# Flight_Computer_R2.net
KiCad netlist of a schematic drawn in EAGLE
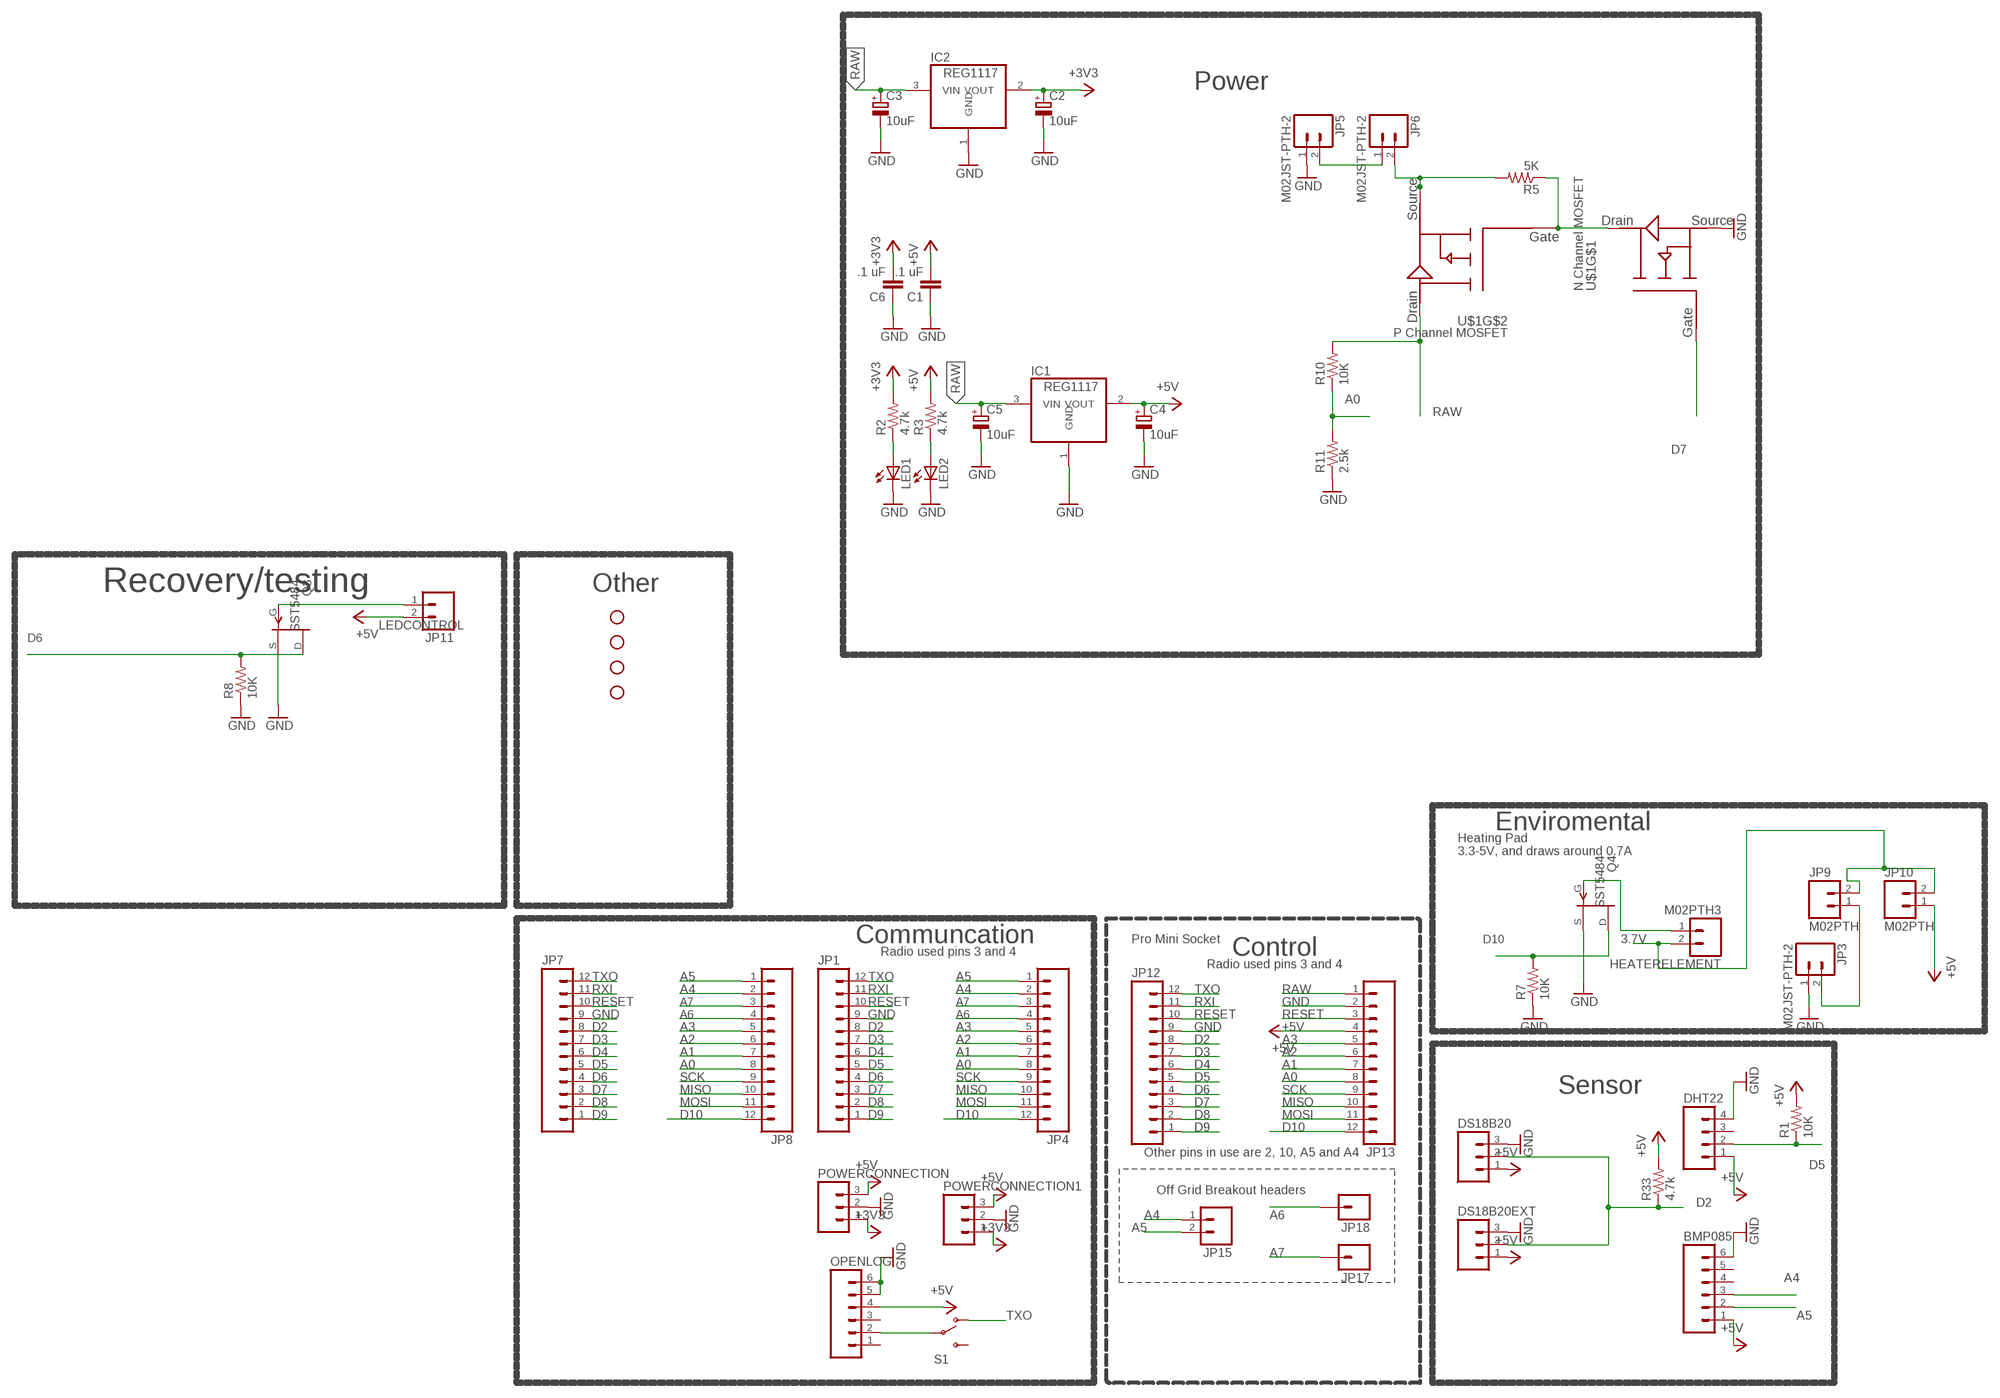
[diagram p0: schematic, sheet 1]

(export (version "E")
  (design (tool "Eeschema 10.0.6"))
  (components
    (comp (ref "BMP085")
      (value "M06SIP")
      (footprint "eagle-import:1X06")
      (libsource (lib "eagle-import") (part "M06SIP"))
    )
    (comp (ref "C1")
      (value ".1 uF")
      (footprint "eagle-import:1206")
      (libsource (lib "eagle-import") (part "CAP1206"))
    )
    (comp (ref "C2")
      (value "10uF")
      (footprint "eagle-import:E2,5-5")
      (libsource (lib "eagle-import") (part "CPOL-EUE2.5-5"))
    )
    (comp (ref "C3")
      (value "10uF")
      (footprint "eagle-import:E2,5-5")
      (libsource (lib "eagle-import") (part "CPOL-EUE2.5-5"))
    )
    (comp (ref "C4")
      (value "10uF")
      (footprint "eagle-import:E2,5-5")
      (libsource (lib "eagle-import") (part "CPOL-EUE2.5-5"))
    )
    (comp (ref "C5")
      (value "10uF")
      (footprint "eagle-import:E2,5-5")
      (libsource (lib "eagle-import") (part "CPOL-EUE2.5-5"))
    )
    (comp (ref "C6")
      (value ".1 uF")
      (footprint "eagle-import:1206")
      (libsource (lib "eagle-import") (part "CAP1206"))
    )
    (comp (ref "DHT22")
      (value "M041X04_NO_SILK")
      (footprint "eagle-import:1X04_NO_SILK")
      (libsource (lib "eagle-import") (part "M041X04_NO_SILK"))
    )
    (comp (ref "DS18B20")
      (value "M03PTH")
      (footprint "eagle-import:1X03")
      (libsource (lib "eagle-import") (part "M03PTH"))
    )
    (comp (ref "DS18B20EXT")
      (value "M03PTH")
      (footprint "eagle-import:1X03")
      (libsource (lib "eagle-import") (part "M03PTH"))
    )
    (comp (ref "HEATERELEMENT")
      (value "M02PTH3")
      (footprint "eagle-import:1X02_LONGPADS")
      (libsource (lib "eagle-import") (part "SparkFun-Connectors_M02PTH3"))
    )
    (comp (ref "IC1")
      (value "REG1117")
      (footprint "eagle-import:SOT223")
      (libsource (lib "eagle-import") (part "REG1117"))
    )
    (comp (ref "IC2")
      (value "REG1117")
      (footprint "eagle-import:SOT223")
      (libsource (lib "eagle-import") (part "REG1117"))
    )
    (comp (ref "JP1")
      (value "M12PTH")
      (footprint "eagle-import:1X12")
      (libsource (lib "eagle-import") (part "M12PTH"))
    )
    (comp (ref "JP3")
      (value "M02JST-PTH-2")
      (footprint "eagle-import:JST-2-PTH")
      (libsource (lib "eagle-import") (part "SparkFun-Connectors_M02JST-PTH-2"))
    )
    (comp (ref "JP4")
      (value "M12PTH")
      (footprint "eagle-import:1X12")
      (libsource (lib "eagle-import") (part "M12PTH"))
    )
    (comp (ref "JP5")
      (value "M02JST-PTH-2")
      (footprint "eagle-import:JST-2-PTH")
      (libsource (lib "eagle-import") (part "SparkFun-Connectors_M02JST-PTH-2"))
    )
    (comp (ref "JP6")
      (value "M02JST-PTH-2")
      (footprint "eagle-import:JST-2-PTH")
      (libsource (lib "eagle-import") (part "SparkFun-Connectors_M02JST-PTH-2"))
    )
    (comp (ref "JP7")
      (value "M12PTH")
      (footprint "eagle-import:1X12")
      (libsource (lib "eagle-import") (part "M12PTH"))
    )
    (comp (ref "JP8")
      (value "M12PTH")
      (footprint "eagle-import:1X12")
      (libsource (lib "eagle-import") (part "M12PTH"))
    )
    (comp (ref "JP9")
      (value "M02PTH")
      (footprint "eagle-import:1X02")
      (libsource (lib "eagle-import") (part "SparkFun-Connectors_M02PTH"))
    )
    (comp (ref "JP10")
      (value "M02PTH")
      (footprint "eagle-import:1X02")
      (libsource (lib "eagle-import") (part "SparkFun-Connectors_M02PTH"))
    )
    (comp (ref "JP11")
      (value "M02PTH")
      (footprint "eagle-import:1X02")
      (libsource (lib "eagle-import") (part "M02PTH"))
    )
    (comp (ref "JP12")
      (value "M12PTH")
      (footprint "eagle-import:1X12")
      (libsource (lib "eagle-import") (part "M12PTH"))
    )
    (comp (ref "JP13")
      (value "M12PTH")
      (footprint "eagle-import:1X12")
      (libsource (lib "eagle-import") (part "M12PTH"))
    )
    (comp (ref "JP15")
      (value "M02PTH")
      (footprint "eagle-import:1X02")
      (libsource (lib "eagle-import") (part "M02PTH"))
    )
    (comp (ref "JP17")
      (value "M01PTH")
      (footprint "eagle-import:1X01")
      (libsource (lib "eagle-import") (part "M01PTH"))
    )
    (comp (ref "JP18")
      (value "M01PTH")
      (footprint "eagle-import:1X01")
      (libsource (lib "eagle-import") (part "M01PTH"))
    )
    (comp (ref "LED1")
      (value "LED3MM")
      (footprint "eagle-import:LED3MM")
      (libsource (lib "eagle-import") (part "LED3MM"))
    )
    (comp (ref "LED2")
      (value "LED3MM")
      (footprint "eagle-import:LED3MM")
      (libsource (lib "eagle-import") (part "LED3MM"))
    )
    (comp (ref "OPENLOG")
      (value "M06SIP")
      (footprint "eagle-import:1X06")
      (libsource (lib "eagle-import") (part "M06SIP"))
    )
    (comp (ref "POWERCONNECTION")
      (value "M03PTH")
      (footprint "eagle-import:1X03")
      (libsource (lib "eagle-import") (part "M03PTH"))
    )
    (comp (ref "POWERCONNECTION1")
      (value "M03PTH")
      (footprint "eagle-import:1X03")
      (libsource (lib "eagle-import") (part "M03PTH"))
    )
    (comp (ref "Q3")
      (value "SST5484")
      (footprint "eagle-import:SOT23")
      (libsource (lib "eagle-import") (part "?548SST4"))
    )
    (comp (ref "Q4")
      (value "SST5484")
      (footprint "eagle-import:SOT23")
      (libsource (lib "eagle-import") (part "?548SST4"))
    )
    (comp (ref "R1")
      (value "10K")
      (footprint "eagle-import:1206")
      (libsource (lib "eagle-import") (part "RESISTOR1206"))
    )
    (comp (ref "R2")
      (value "4.7k")
      (footprint "eagle-import:1206")
      (libsource (lib "eagle-import") (part "RESISTOR1206"))
    )
    (comp (ref "R3")
      (value "4.7k")
      (footprint "eagle-import:1206")
      (libsource (lib "eagle-import") (part "RESISTOR1206"))
    )
    (comp (ref "R5")
      (value "5K")
      (footprint "eagle-import:1206")
      (libsource (lib "eagle-import") (part "RESISTOR1206"))
    )
    (comp (ref "R7")
      (value "10K")
      (footprint "eagle-import:1206")
      (libsource (lib "eagle-import") (part "RESISTOR1206"))
    )
    (comp (ref "R8")
      (value "10K")
      (footprint "eagle-import:1206")
      (libsource (lib "eagle-import") (part "RESISTOR1206"))
    )
    (comp (ref "R10")
      (value "10K")
      (footprint "eagle-import:1206")
      (libsource (lib "eagle-import") (part "RESISTOR1206"))
    )
    (comp (ref "R11")
      (value "2.5k")
      (footprint "eagle-import:1206")
      (libsource (lib "eagle-import") (part "RESISTOR1206"))
    )
    (comp (ref "R33")
      (value "4.7k")
      (footprint "eagle-import:1206")
      (libsource (lib "eagle-import") (part "RESISTOR1206"))
    )
    (comp (ref "S1")
      (value "SWITCH-SPDTPTH")
      (footprint "eagle-import:SWITCH-SPDT")
      (libsource (lib "eagle-import") (part "SWITCH-SPDTPTH"))
    )
    (comp (ref "STANDOFF1")
      (value "STAND-OFF")
      (footprint "eagle-import:STAND-OFF")
      (libsource (lib "eagle-import") (part "STAND-OFF"))
    )
    (comp (ref "STANDOFF2")
      (value "STAND-OFF")
      (footprint "eagle-import:STAND-OFF")
      (libsource (lib "eagle-import") (part "STAND-OFF"))
    )
    (comp (ref "STANDOFF3")
      (value "STAND-OFF")
      (footprint "eagle-import:STAND-OFF")
      (libsource (lib "eagle-import") (part "STAND-OFF"))
    )
    (comp (ref "STANDOFF4")
      (value "STAND-OFF")
      (footprint "eagle-import:STAND-OFF")
      (libsource (lib "eagle-import") (part "STAND-OFF"))
    )
    (comp (ref "U$1")
      (value "IRF9389TRPBF")
      (footprint "eagle-import:SO-8")
      (libsource (lib "eagle-import") (part "IRF9389TRPBF"))
    )
  )
  (nets
    (net (code "1") (name "+3V3") (class "Default")
      (node (ref "C2") (pin "+") (pinfunction "+_+") (pintype "passive"))
      (node (ref "C6") (pin "2") (pinfunction "2_2") (pintype "passive"))
      (node (ref "IC2") (pin "2") (pinfunction "VOUT_2") (pintype "output"))
      (node (ref "POWERCONNECTION") (pin "1") (pinfunction "1_1") (pintype "passive"))
      (node (ref "POWERCONNECTION1") (pin "1") (pinfunction "1_1") (pintype "passive"))
      (node (ref "R2") (pin "2") (pinfunction "2_2") (pintype "passive"))
    )
    (net (code "2") (name "+5V") (class "Default")
      (node (ref "BMP085") (pin "1") (pinfunction "1_1") (pintype "passive"))
      (node (ref "C1") (pin "2") (pinfunction "2_2") (pintype "passive"))
      (node (ref "C4") (pin "+") (pinfunction "+_+") (pintype "passive"))
      (node (ref "DHT22") (pin "1") (pinfunction "1_1") (pintype "passive"))
      (node (ref "DS18B20") (pin "1") (pinfunction "1_1") (pintype "passive"))
      (node (ref "DS18B20EXT") (pin "1") (pinfunction "1_1") (pintype "passive"))
      (node (ref "IC1") (pin "2") (pinfunction "VOUT_2") (pintype "output"))
      (node (ref "JP10") (pin "1") (pinfunction "1_1") (pintype "passive"))
      (node (ref "JP11") (pin "2") (pinfunction "2_2") (pintype "passive"))
      (node (ref "JP13") (pin "4") (pinfunction "4_4") (pintype "passive"))
      (node (ref "OPENLOG") (pin "4") (pinfunction "4_4") (pintype "passive"))
      (node (ref "POWERCONNECTION") (pin "3") (pinfunction "3_3") (pintype "passive"))
      (node (ref "POWERCONNECTION1") (pin "3") (pinfunction "3_3") (pintype "passive"))
      (node (ref "R1") (pin "2") (pinfunction "2_2") (pintype "passive"))
      (node (ref "R3") (pin "2") (pinfunction "2_2") (pintype "passive"))
      (node (ref "R33") (pin "2") (pinfunction "2_2") (pintype "passive"))
    )
    (net (code "3") (name "/3.7V") (class "Default")
      (node (ref "HEATERELEMENT") (pin "2") (pinfunction "2_2") (pintype "passive"))
      (node (ref "JP10") (pin "2") (pinfunction "2_2") (pintype "passive"))
      (node (ref "JP9") (pin "2") (pinfunction "2_2") (pintype "passive"))
    )
    (net (code "4") (name "/A0") (class "Default")
      (node (ref "JP13") (pin "8") (pinfunction "8_8") (pintype "passive"))
      (node (ref "JP4") (pin "8") (pinfunction "8_8") (pintype "passive"))
      (node (ref "JP8") (pin "8") (pinfunction "8_8") (pintype "passive"))
      (node (ref "R10") (pin "1") (pinfunction "1_1") (pintype "passive"))
      (node (ref "R11") (pin "2") (pinfunction "2_2") (pintype "passive"))
    )
    (net (code "5") (name "/A1") (class "Default")
      (node (ref "JP13") (pin "7") (pinfunction "7_7") (pintype "passive"))
      (node (ref "JP4") (pin "7") (pinfunction "7_7") (pintype "passive"))
      (node (ref "JP8") (pin "7") (pinfunction "7_7") (pintype "passive"))
    )
    (net (code "6") (name "/A2") (class "Default")
      (node (ref "JP13") (pin "6") (pinfunction "6_6") (pintype "passive"))
      (node (ref "JP4") (pin "6") (pinfunction "6_6") (pintype "passive"))
      (node (ref "JP8") (pin "6") (pinfunction "6_6") (pintype "passive"))
    )
    (net (code "7") (name "/A3") (class "Default")
      (node (ref "JP13") (pin "5") (pinfunction "5_5") (pintype "passive"))
      (node (ref "JP4") (pin "5") (pinfunction "5_5") (pintype "passive"))
      (node (ref "JP8") (pin "5") (pinfunction "5_5") (pintype "passive"))
    )
    (net (code "8") (name "/A4") (class "Default")
      (node (ref "BMP085") (pin "3") (pinfunction "3_3") (pintype "passive"))
      (node (ref "JP15") (pin "1") (pinfunction "1_1") (pintype "passive"))
      (node (ref "JP4") (pin "2") (pinfunction "2_2") (pintype "passive"))
      (node (ref "JP8") (pin "2") (pinfunction "2_2") (pintype "passive"))
    )
    (net (code "9") (name "/A5") (class "Default")
      (node (ref "BMP085") (pin "2") (pinfunction "2_2") (pintype "passive"))
      (node (ref "JP15") (pin "2") (pinfunction "2_2") (pintype "passive"))
      (node (ref "JP4") (pin "1") (pinfunction "1_1") (pintype "passive"))
      (node (ref "JP8") (pin "1") (pinfunction "1_1") (pintype "passive"))
    )
    (net (code "10") (name "/A6") (class "Default")
      (node (ref "JP18") (pin "1") (pinfunction "1_1") (pintype "passive"))
      (node (ref "JP4") (pin "4") (pinfunction "4_4") (pintype "passive"))
      (node (ref "JP8") (pin "4") (pinfunction "4_4") (pintype "passive"))
    )
    (net (code "11") (name "/A7") (class "Default")
      (node (ref "JP17") (pin "1") (pinfunction "1_1") (pintype "passive"))
      (node (ref "JP4") (pin "3") (pinfunction "3_3") (pintype "passive"))
      (node (ref "JP8") (pin "3") (pinfunction "3_3") (pintype "passive"))
    )
    (net (code "12") (name "/D2") (class "Default")
      (node (ref "DS18B20") (pin "2") (pinfunction "2_2") (pintype "passive"))
      (node (ref "DS18B20EXT") (pin "2") (pinfunction "2_2") (pintype "passive"))
      (node (ref "JP1") (pin "8") (pinfunction "8_8") (pintype "passive"))
      (node (ref "JP12") (pin "8") (pinfunction "8_8") (pintype "passive"))
      (node (ref "JP7") (pin "8") (pinfunction "8_8") (pintype "passive"))
      (node (ref "R33") (pin "1") (pinfunction "1_1") (pintype "passive"))
    )
    (net (code "13") (name "/D3") (class "Default")
      (node (ref "JP1") (pin "7") (pinfunction "7_7") (pintype "passive"))
      (node (ref "JP12") (pin "7") (pinfunction "7_7") (pintype "passive"))
      (node (ref "JP7") (pin "7") (pinfunction "7_7") (pintype "passive"))
    )
    (net (code "14") (name "/D4") (class "Default")
      (node (ref "JP1") (pin "6") (pinfunction "6_6") (pintype "passive"))
      (node (ref "JP12") (pin "6") (pinfunction "6_6") (pintype "passive"))
      (node (ref "JP7") (pin "6") (pinfunction "6_6") (pintype "passive"))
    )
    (net (code "15") (name "/D5") (class "Default")
      (node (ref "DHT22") (pin "2") (pinfunction "2_2") (pintype "passive"))
      (node (ref "JP1") (pin "5") (pinfunction "5_5") (pintype "passive"))
      (node (ref "JP12") (pin "5") (pinfunction "5_5") (pintype "passive"))
      (node (ref "JP7") (pin "5") (pinfunction "5_5") (pintype "passive"))
      (node (ref "R1") (pin "1") (pinfunction "1_1") (pintype "passive"))
    )
    (net (code "16") (name "/D6") (class "Default")
      (node (ref "JP1") (pin "4") (pinfunction "4_4") (pintype "passive"))
      (node (ref "JP12") (pin "4") (pinfunction "4_4") (pintype "passive"))
      (node (ref "JP7") (pin "4") (pinfunction "4_4") (pintype "passive"))
      (node (ref "Q3") (pin "1") (pinfunction "D_1") (pintype "passive"))
      (node (ref "R8") (pin "2") (pinfunction "2_2") (pintype "passive"))
    )
    (net (code "17") (name "/D7") (class "Default")
      (node (ref "JP1") (pin "3") (pinfunction "3_3") (pintype "passive"))
      (node (ref "JP12") (pin "3") (pinfunction "3_3") (pintype "passive"))
      (node (ref "JP7") (pin "3") (pinfunction "3_3") (pintype "passive"))
      (node (ref "U$1") (pin "2") (pinfunction "GATE_2") (pintype "input"))
    )
    (net (code "18") (name "/D8") (class "Default")
      (node (ref "JP1") (pin "2") (pinfunction "2_2") (pintype "passive"))
      (node (ref "JP12") (pin "2") (pinfunction "2_2") (pintype "passive"))
      (node (ref "JP7") (pin "2") (pinfunction "2_2") (pintype "passive"))
    )
    (net (code "19") (name "/D9") (class "Default")
      (node (ref "JP1") (pin "1") (pinfunction "1_1") (pintype "passive"))
      (node (ref "JP12") (pin "1") (pinfunction "1_1") (pintype "passive"))
      (node (ref "JP7") (pin "1") (pinfunction "1_1") (pintype "passive"))
    )
    (net (code "20") (name "/D10") (class "Default")
      (node (ref "JP13") (pin "12") (pinfunction "12_12") (pintype "passive"))
      (node (ref "JP4") (pin "12") (pinfunction "12_12") (pintype "passive"))
      (node (ref "JP8") (pin "12") (pinfunction "12_12") (pintype "passive"))
      (node (ref "Q4") (pin "1") (pinfunction "D_1") (pintype "passive"))
      (node (ref "R7") (pin "2") (pinfunction "2_2") (pintype "passive"))
    )
    (net (code "21") (name "/LEDCONTROL") (class "Default")
      (node (ref "JP11") (pin "1") (pinfunction "1_1") (pintype "passive"))
      (node (ref "Q3") (pin "3") (pinfunction "G_3") (pintype "passive"))
    )
    (net (code "22") (name "/MISO") (class "Default")
      (node (ref "JP13") (pin "10") (pinfunction "10_10") (pintype "passive"))
      (node (ref "JP4") (pin "10") (pinfunction "10_10") (pintype "passive"))
      (node (ref "JP8") (pin "10") (pinfunction "10_10") (pintype "passive"))
    )
    (net (code "23") (name "/MOSI") (class "Default")
      (node (ref "JP13") (pin "11") (pinfunction "11_11") (pintype "passive"))
      (node (ref "JP4") (pin "11") (pinfunction "11_11") (pintype "passive"))
      (node (ref "JP8") (pin "11") (pinfunction "11_11") (pintype "passive"))
    )
    (net (code "24") (name "/RESET") (class "Default")
      (node (ref "JP1") (pin "10") (pinfunction "10_10") (pintype "passive"))
      (node (ref "JP12") (pin "10") (pinfunction "10_10") (pintype "passive"))
      (node (ref "JP13") (pin "3") (pinfunction "3_3") (pintype "passive"))
      (node (ref "JP7") (pin "10") (pinfunction "10_10") (pintype "passive"))
    )
    (net (code "25") (name "/RXI") (class "Default")
      (node (ref "JP1") (pin "11") (pinfunction "11_11") (pintype "passive"))
      (node (ref "JP12") (pin "11") (pinfunction "11_11") (pintype "passive"))
      (node (ref "JP7") (pin "11") (pinfunction "11_11") (pintype "passive"))
    )
    (net (code "26") (name "/SCK") (class "Default")
      (node (ref "JP13") (pin "9") (pinfunction "9_9") (pintype "passive"))
      (node (ref "JP4") (pin "9") (pinfunction "9_9") (pintype "passive"))
      (node (ref "JP8") (pin "9") (pinfunction "9_9") (pintype "passive"))
    )
    (net (code "27") (name "/TXO") (class "Default")
      (node (ref "JP1") (pin "12") (pinfunction "12_12") (pintype "passive"))
      (node (ref "JP12") (pin "12") (pinfunction "12_12") (pintype "passive"))
      (node (ref "JP7") (pin "12") (pinfunction "12_12") (pintype "passive"))
      (node (ref "S1") (pin "1") (pinfunction "O_1") (pintype "passive"))
    )
    (net (code "28") (name "GND") (class "Default")
      (node (ref "BMP085") (pin "6") (pinfunction "6_6") (pintype "passive"))
      (node (ref "C1") (pin "1") (pinfunction "1_1") (pintype "passive"))
      (node (ref "C2") (pin "-") (pinfunction "-_-") (pintype "passive"))
      (node (ref "C3") (pin "-") (pinfunction "-_-") (pintype "passive"))
      (node (ref "C4") (pin "-") (pinfunction "-_-") (pintype "passive"))
      (node (ref "C5") (pin "-") (pinfunction "-_-") (pintype "passive"))
      (node (ref "C6") (pin "1") (pinfunction "1_1") (pintype "passive"))
      (node (ref "DHT22") (pin "4") (pinfunction "4_4") (pintype "passive"))
      (node (ref "DS18B20") (pin "3") (pinfunction "3_3") (pintype "passive"))
      (node (ref "DS18B20EXT") (pin "3") (pinfunction "3_3") (pintype "passive"))
      (node (ref "IC1") (pin "1") (pinfunction "GND_1") (pintype "power_in"))
      (node (ref "IC2") (pin "1") (pinfunction "GND_1") (pintype "power_in"))
      (node (ref "JP1") (pin "9") (pinfunction "9_9") (pintype "passive"))
      (node (ref "JP12") (pin "9") (pinfunction "9_9") (pintype "passive"))
      (node (ref "JP13") (pin "2") (pinfunction "2_2") (pintype "passive"))
      (node (ref "JP3") (pin "1") (pinfunction "1_1") (pintype "passive"))
      (node (ref "JP5") (pin "1") (pinfunction "1_1") (pintype "passive"))
      (node (ref "JP7") (pin "9") (pinfunction "9_9") (pintype "passive"))
      (node (ref "LED1") (pin "K") (pinfunction "C_K") (pintype "passive"))
      (node (ref "LED2") (pin "K") (pinfunction "C_K") (pintype "passive"))
      (node (ref "OPENLOG") (pin "5") (pinfunction "5_5") (pintype "passive"))
      (node (ref "OPENLOG") (pin "6") (pinfunction "6_6") (pintype "passive"))
      (node (ref "POWERCONNECTION") (pin "2") (pinfunction "2_2") (pintype "passive"))
      (node (ref "POWERCONNECTION1") (pin "2") (pinfunction "2_2") (pintype "passive"))
      (node (ref "Q3") (pin "2") (pinfunction "S_2") (pintype "passive"))
      (node (ref "Q4") (pin "2") (pinfunction "S_2") (pintype "passive"))
      (node (ref "R11") (pin "1") (pinfunction "1_1") (pintype "passive"))
      (node (ref "R7") (pin "1") (pinfunction "1_1") (pintype "passive"))
      (node (ref "R8") (pin "1") (pinfunction "1_1") (pintype "passive"))
      (node (ref "U$1") (pin "1") (pinfunction "SOURCE_1") (pintype "bidirectional"))
    )
    (net (code "29") (name "Net-(JP3-Pad2)") (class "Default")
      (node (ref "JP3") (pin "2") (pinfunction "2_2") (pintype "passive"))
      (node (ref "JP9") (pin "1") (pinfunction "1_1") (pintype "passive"))
    )
    (net (code "30") (name "Net-(JP5-Pad2)") (class "Default")
      (node (ref "JP5") (pin "2") (pinfunction "2_2") (pintype "passive"))
      (node (ref "JP6") (pin "1") (pinfunction "1_1") (pintype "passive"))
    )
    (net (code "31") (name "Net-(LED1-PadA)") (class "Default")
      (node (ref "LED1") (pin "A") (pinfunction "A_A") (pintype "passive"))
      (node (ref "R2") (pin "1") (pinfunction "1_1") (pintype "passive"))
    )
    (net (code "32") (name "Net-(LED2-PadA)") (class "Default")
      (node (ref "LED2") (pin "A") (pinfunction "A_A") (pintype "passive"))
      (node (ref "R3") (pin "1") (pinfunction "1_1") (pintype "passive"))
    )
    (net (code "33") (name "Net-(Q4-G)") (class "Default")
      (node (ref "HEATERELEMENT") (pin "1") (pinfunction "1_1") (pintype "passive"))
      (node (ref "Q4") (pin "3") (pinfunction "G_3") (pintype "passive"))
    )
    (net (code "34") (name "Net-(S1-P)") (class "Default")
      (node (ref "OPENLOG") (pin "2") (pinfunction "2_2") (pintype "passive"))
      (node (ref "S1") (pin "2") (pinfunction "P_2") (pintype "passive"))
    )
    (net (code "35") (name "Net-(U$1A-DRAIN)") (class "Default")
      (node (ref "R5") (pin "1") (pinfunction "1_1") (pintype "passive"))
      (node (ref "U$1") (pin "4") (pinfunction "GATE_4") (pintype "input"))
      (node (ref "U$1") (pin "7") (pinfunction "DRAIN_7") (pintype "bidirectional"))
    )
    (net (code "36") (name "Net-(U$1B-SOURCE)") (class "Default")
      (node (ref "JP6") (pin "2") (pinfunction "2_2") (pintype "passive"))
      (node (ref "R5") (pin "2") (pinfunction "2_2") (pintype "passive"))
      (node (ref "U$1") (pin "3") (pinfunction "SOURCE_3") (pintype "bidirectional"))
    )
    (net (code "37") (name "RAW") (class "Default")
      (node (ref "C3") (pin "+") (pinfunction "+_+") (pintype "passive"))
      (node (ref "C5") (pin "+") (pinfunction "+_+") (pintype "passive"))
      (node (ref "IC1") (pin "3") (pinfunction "VIN_3") (pintype "input"))
      (node (ref "IC2") (pin "3") (pinfunction "VIN_3") (pintype "input"))
      (node (ref "JP13") (pin "1") (pinfunction "1_1") (pintype "passive"))
      (node (ref "R10") (pin "2") (pinfunction "2_2") (pintype "passive"))
      (node (ref "U$1") (pin "5") (pinfunction "DRAIN_5") (pintype "bidirectional"))
    )
    (net (code "38") (name "unconnected-(BMP085-Pad4)") (class "Default")
      (node (ref "BMP085") (pin "4") (pinfunction "4_4") (pintype "passive"))
    )
    (net (code "39") (name "unconnected-(BMP085-Pad5)") (class "Default")
      (node (ref "BMP085") (pin "5") (pinfunction "5_5") (pintype "passive"))
    )
    (net (code "40") (name "unconnected-(DHT22-Pad3)") (class "Default")
      (node (ref "DHT22") (pin "3") (pinfunction "3_3") (pintype "passive"))
    )
    (net (code "41") (name "unconnected-(OPENLOG-Pad1)") (class "Default")
      (node (ref "OPENLOG") (pin "1") (pinfunction "1_1") (pintype "passive"))
    )
    (net (code "42") (name "unconnected-(OPENLOG-Pad3)") (class "Default")
      (node (ref "OPENLOG") (pin "3") (pinfunction "3_3") (pintype "passive"))
    )
    (net (code "43") (name "unconnected-(S1-S-Pad3)") (class "Default")
      (node (ref "S1") (pin "3") (pinfunction "S_3") (pintype "passive"))
    )
  )
)
